# Clock_Distribution.net
KiCad netlist of a schematic drawn in Altium Designer
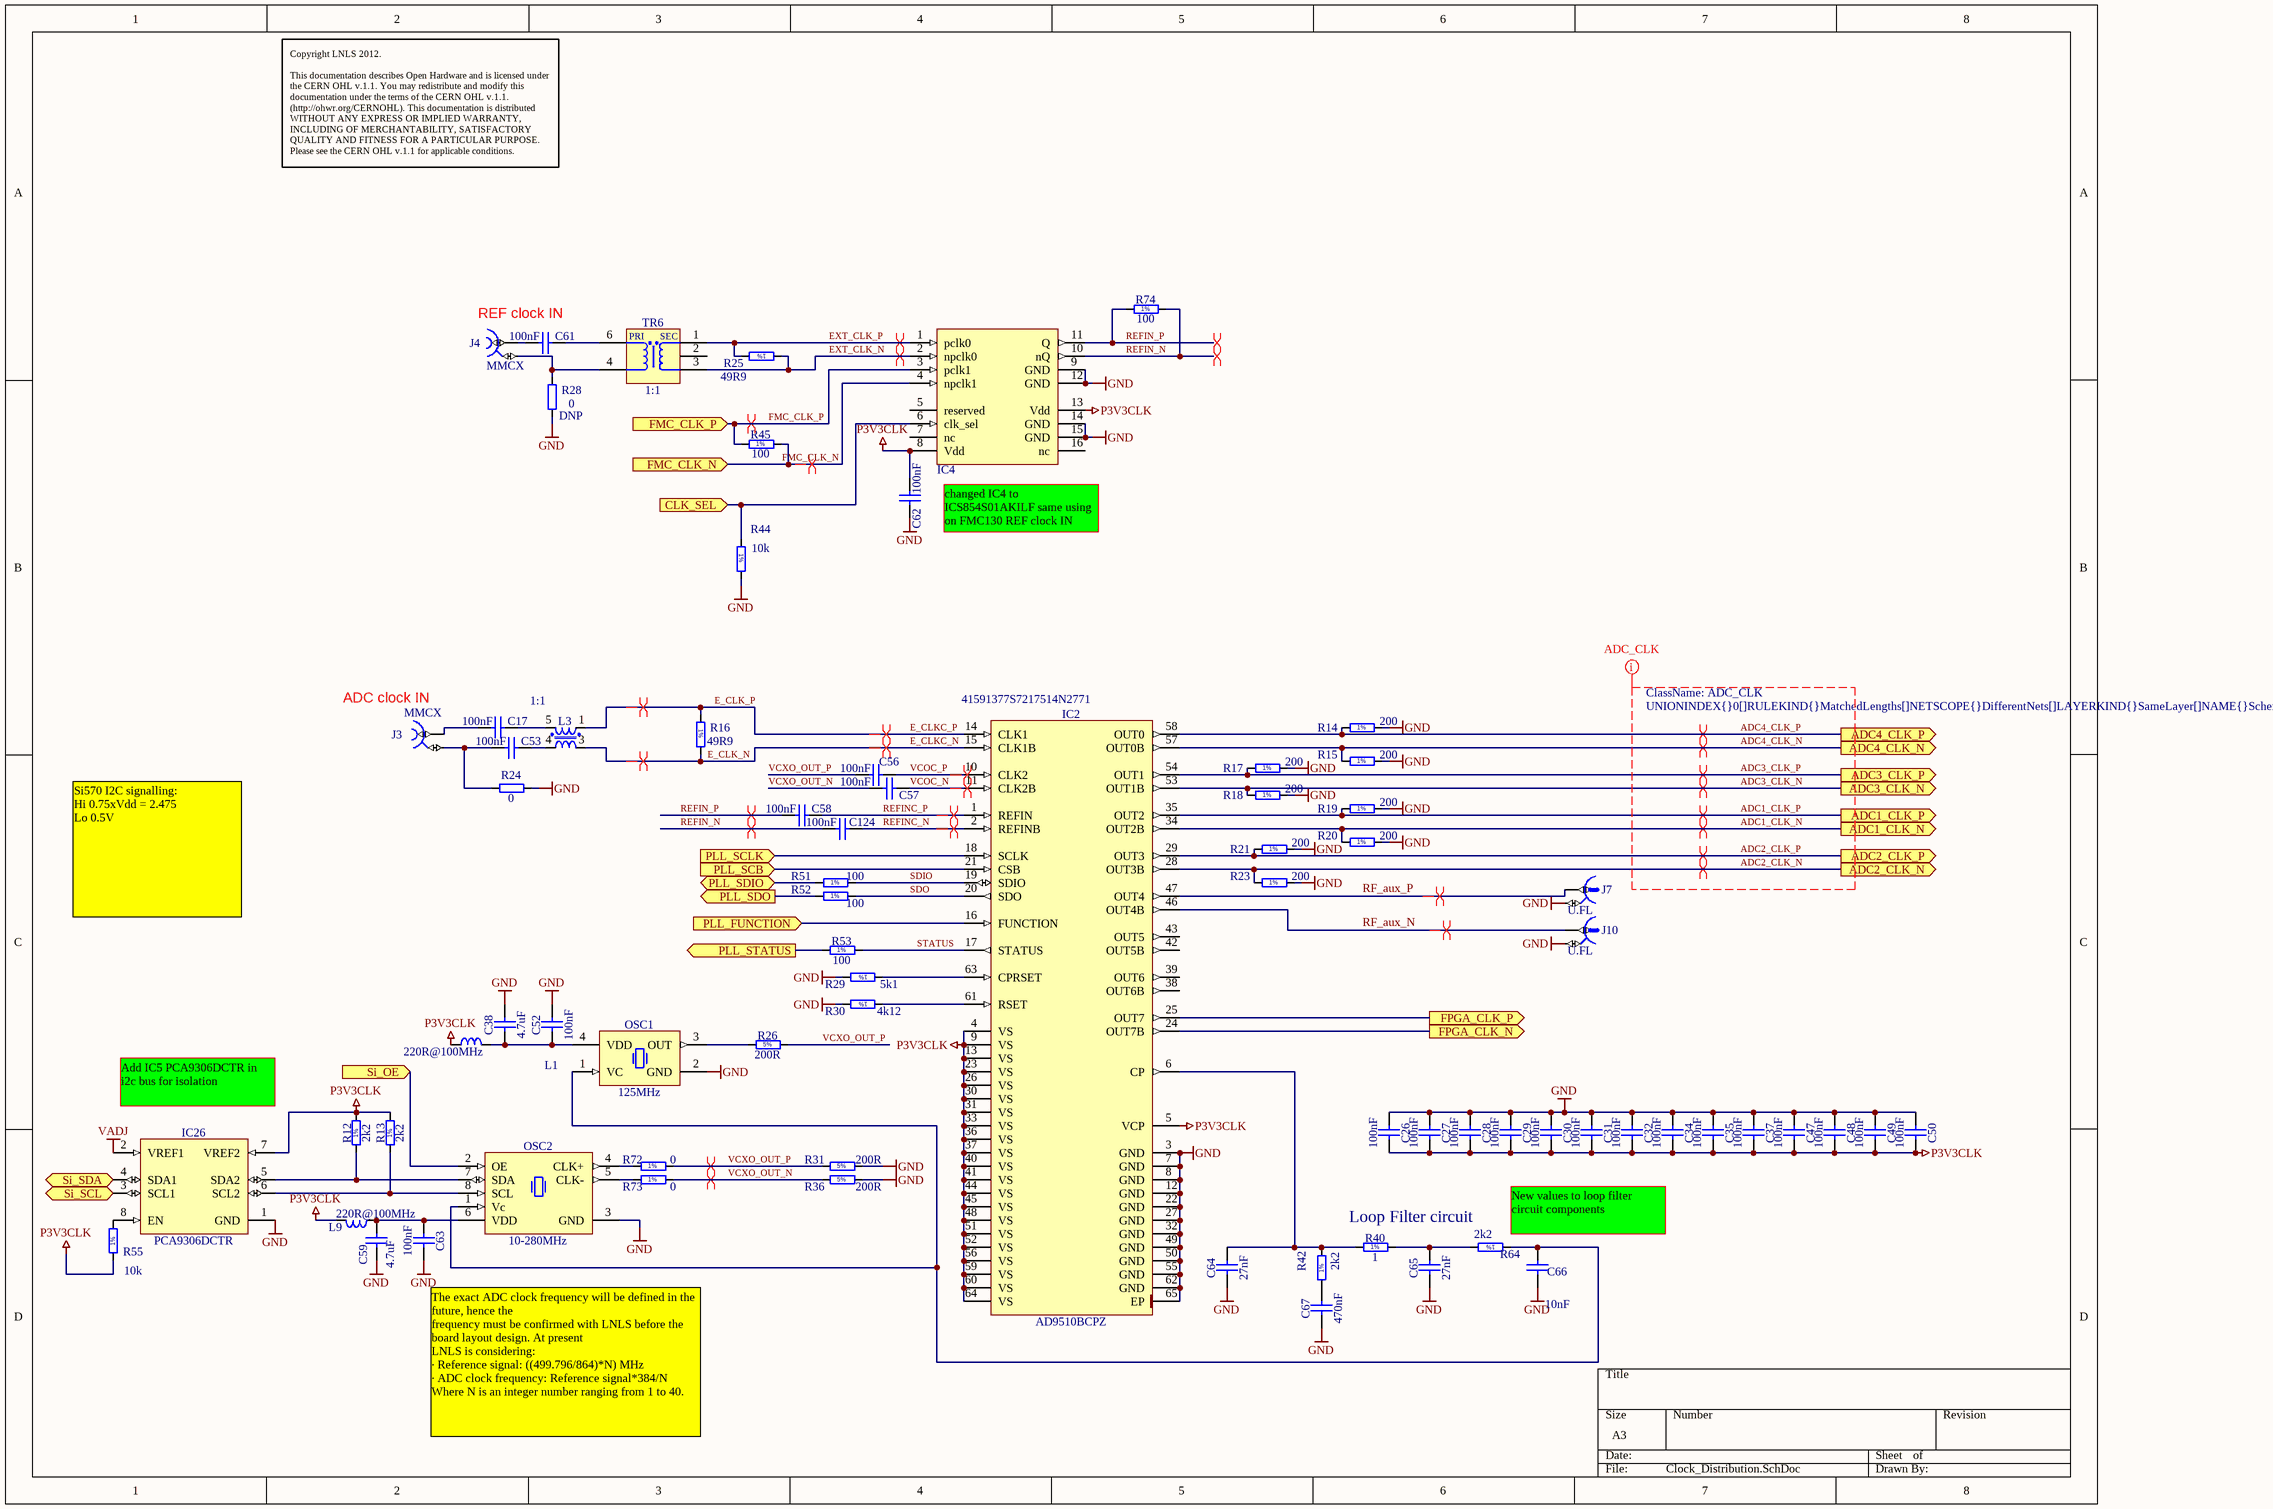
[diagram p0: Clock_Distribution.SchDoc]

(export (version "E")
  (design (tool "Eeschema 10.0.6"))
  (components
    (comp (ref "C17")
      (value "100nF")
      (footprint "CAPC0603X33N")
      (description "Non-polarised capacitor")
      (fields
        (field (name "PART NUMBER") "CC0201_100NF_6.3V_10%_X5R")
        (field (name "VOLTAGE") "6.3V")
        (field (name "AUTHOR") "CERN DEM JLC")
      )
      (libsource (lib "Capacitors") (part "Capacitor - non polarized"))
    )
    (comp (ref "C26")
      (value "100nF")
      (footprint "CAPC0603X33N")
      (description "Non-polarised capacitor")
      (fields
        (field (name "PART NUMBER") "CC0201_100NF_6.3V_10%_X5R")
        (field (name "VOLTAGE") "6.3V")
        (field (name "AUTHOR") "CERN DEM JLC")
      )
      (libsource (lib "Capacitors") (part "Capacitor - non polarized"))
    )
    (comp (ref "C27")
      (value "100nF")
      (footprint "CAPC0603X33N")
      (description "Non-polarised capacitor")
      (fields
        (field (name "PART NUMBER") "CC0201_100NF_6.3V_10%_X5R")
        (field (name "VOLTAGE") "6.3V")
        (field (name "AUTHOR") "CERN DEM JLC")
      )
      (libsource (lib "Capacitors") (part "Capacitor - non polarized"))
    )
    (comp (ref "C28")
      (value "100nF")
      (footprint "CAPC0603X33N")
      (description "Non-polarised capacitor")
      (fields
        (field (name "PART NUMBER") "CC0201_100NF_6.3V_10%_X5R")
        (field (name "VOLTAGE") "6.3V")
        (field (name "AUTHOR") "CERN DEM JLC")
      )
      (libsource (lib "Capacitors") (part "Capacitor - non polarized"))
    )
    (comp (ref "C29")
      (value "100nF")
      (footprint "CAPC0603X33N")
      (description "Non-polarised capacitor")
      (fields
        (field (name "PART NUMBER") "CC0201_100NF_6.3V_10%_X5R")
        (field (name "VOLTAGE") "6.3V")
        (field (name "AUTHOR") "CERN DEM JLC")
      )
      (libsource (lib "Capacitors") (part "Capacitor - non polarized"))
    )
    (comp (ref "C30")
      (value "100nF")
      (footprint "CAPC0603X33N")
      (description "Non-polarised capacitor")
      (fields
        (field (name "PART NUMBER") "CC0201_100NF_6.3V_10%_X5R")
        (field (name "VOLTAGE") "6.3V")
        (field (name "AUTHOR") "CERN DEM JLC")
      )
      (libsource (lib "Capacitors") (part "Capacitor - non polarized"))
    )
    (comp (ref "C31")
      (value "100nF")
      (footprint "CAPC0603X33N")
      (description "Non-polarised capacitor")
      (fields
        (field (name "PART NUMBER") "CC0201_100NF_6.3V_10%_X5R")
        (field (name "VOLTAGE") "6.3V")
        (field (name "AUTHOR") "CERN DEM JLC")
      )
      (libsource (lib "Capacitors") (part "Capacitor - non polarized"))
    )
    (comp (ref "C32")
      (value "100nF")
      (footprint "CAPC0603X33N")
      (description "Non-polarised capacitor")
      (fields
        (field (name "PART NUMBER") "CC0201_100NF_6.3V_10%_X5R")
        (field (name "VOLTAGE") "6.3V")
        (field (name "AUTHOR") "CERN DEM JLC")
      )
      (libsource (lib "Capacitors") (part "Capacitor - non polarized"))
    )
    (comp (ref "C34")
      (value "100nF")
      (footprint "CAPC0603X33N")
      (description "Non-polarised capacitor")
      (fields
        (field (name "PART NUMBER") "CC0201_100NF_6.3V_10%_X5R")
        (field (name "VOLTAGE") "6.3V")
        (field (name "AUTHOR") "CERN DEM JLC")
      )
      (libsource (lib "Capacitors") (part "Capacitor - non polarized"))
    )
    (comp (ref "C35")
      (value "100nF")
      (footprint "CAPC0603X33N")
      (description "Non-polarised capacitor")
      (fields
        (field (name "PART NUMBER") "CC0201_100NF_6.3V_10%_X5R")
        (field (name "VOLTAGE") "6.3V")
        (field (name "AUTHOR") "CERN DEM JLC")
      )
      (libsource (lib "Capacitors") (part "Capacitor - non polarized"))
    )
    (comp (ref "C37")
      (value "100nF")
      (footprint "CAPC0603X33N")
      (description "Non-polarised capacitor")
      (fields
        (field (name "PART NUMBER") "CC0201_100NF_6.3V_10%_X5R")
        (field (name "VOLTAGE") "6.3V")
        (field (name "AUTHOR") "CERN DEM JLC")
      )
      (libsource (lib "Capacitors") (part "Capacitor - non polarized"))
    )
    (comp (ref "C38")
      (value "4.7uF")
      (footprint "CAPC1608X87N")
      (description "Non-polarised capacitor")
      (fields
        (field (name "PART NUMBER") "CC0603_4.7UF_6.3V_10%_X5R")
        (field (name "VOLTAGE") "6.3V")
        (field (name "AUTHOR") "CERN DEM JLC")
      )
      (libsource (lib "Capacitors") (part "Capacitor - non polarized"))
    )
    (comp (ref "C47")
      (value "100nF")
      (footprint "CAPC0603X33N")
      (description "Non-polarised capacitor")
      (fields
        (field (name "PART NUMBER") "CC0201_100NF_6.3V_10%_X5R")
        (field (name "VOLTAGE") "6.3V")
        (field (name "AUTHOR") "CERN DEM JLC")
      )
      (libsource (lib "Capacitors") (part "Capacitor - non polarized"))
    )
    (comp (ref "C48")
      (value "100nF")
      (footprint "CAPC0603X33N")
      (description "Non-polarised capacitor")
      (fields
        (field (name "PART NUMBER") "CC0201_100NF_6.3V_10%_X5R")
        (field (name "VOLTAGE") "6.3V")
        (field (name "AUTHOR") "CERN DEM JLC")
      )
      (libsource (lib "Capacitors") (part "Capacitor - non polarized"))
    )
    (comp (ref "C49")
      (value "100nF")
      (footprint "CAPC0603X33N")
      (description "Non-polarised capacitor")
      (fields
        (field (name "PART NUMBER") "CC0201_100NF_6.3V_10%_X5R")
        (field (name "VOLTAGE") "6.3V")
        (field (name "AUTHOR") "CERN DEM JLC")
      )
      (libsource (lib "Capacitors") (part "Capacitor - non polarized"))
    )
    (comp (ref "C50")
      (value "100nF")
      (footprint "CAPC0603X33N")
      (description "Non-polarised capacitor")
      (fields
        (field (name "PART NUMBER") "CC0201_100NF_6.3V_10%_X5R")
        (field (name "VOLTAGE") "6.3V")
        (field (name "AUTHOR") "CERN DEM JLC")
      )
      (libsource (lib "Capacitors") (part "Capacitor - non polarized"))
    )
    (comp (ref "C52")
      (value "100nF")
      (footprint "CAPC0603X33N")
      (description "Non-polarised capacitor")
      (fields
        (field (name "PART NUMBER") "CC0201_100NF_6.3V_10%_X5R")
        (field (name "VOLTAGE") "6.3V")
        (field (name "AUTHOR") "CERN DEM JLC")
      )
      (libsource (lib "Capacitors") (part "Capacitor - non polarized"))
    )
    (comp (ref "C53")
      (value "100nF")
      (footprint "CAPC0603X33N")
      (description "Non-polarised capacitor")
      (fields
        (field (name "PART NUMBER") "CC0201_100NF_6.3V_10%_X5R")
        (field (name "VOLTAGE") "6.3V")
        (field (name "AUTHOR") "CERN DEM JLC")
      )
      (libsource (lib "Capacitors") (part "Capacitor - non polarized"))
    )
    (comp (ref "C56")
      (value "100nF")
      (footprint "CAPC0603X33N")
      (description "Non-polarised capacitor")
      (fields
        (field (name "PART NUMBER") "CC0201_100NF_6.3V_10%_X5R")
        (field (name "VOLTAGE") "6.3V")
        (field (name "AUTHOR") "CERN DEM JLC")
      )
      (libsource (lib "Capacitors") (part "Capacitor - non polarized"))
    )
    (comp (ref "C57")
      (value "100nF")
      (footprint "CAPC0603X33N")
      (description "Non-polarised capacitor")
      (fields
        (field (name "PART NUMBER") "CC0201_100NF_6.3V_10%_X5R")
        (field (name "VOLTAGE") "6.3V")
        (field (name "AUTHOR") "CERN DEM JLC")
      )
      (libsource (lib "Capacitors") (part "Capacitor - non polarized"))
    )
    (comp (ref "C58")
      (value "100nF")
      (footprint "CAPC0603X33N")
      (description "Non-polarised capacitor")
      (fields
        (field (name "PART NUMBER") "CC0201_100NF_6.3V_10%_X5R")
        (field (name "VOLTAGE") "6.3V")
        (field (name "AUTHOR") "CERN DEM JLC")
      )
      (libsource (lib "Capacitors") (part "Capacitor - non polarized"))
    )
    (comp (ref "C59")
      (value "4.7uF")
      (footprint "CAPC1608X87N")
      (description "Non-polarised capacitor")
      (fields
        (field (name "PART NUMBER") "CC0603_4.7UF_6.3V_10%_X5R")
        (field (name "VOLTAGE") "6.3V")
        (field (name "AUTHOR") "CERN DEM JLC")
      )
      (libsource (lib "Capacitors") (part "Capacitor - non polarized"))
    )
    (comp (ref "C61")
      (value "100nF")
      (footprint "CAPC0603X33N")
      (description "Non-polarised capacitor")
      (fields
        (field (name "PART NUMBER") "CC0201_100NF_6.3V_10%_X5R")
        (field (name "VOLTAGE") "6.3V")
        (field (name "AUTHOR") "CERN DEM JLC")
      )
      (libsource (lib "Capacitors") (part "Capacitor - non polarized"))
    )
    (comp (ref "C62")
      (value "100nF")
      (footprint "CAPC0603X33N")
      (description "Non-polarised capacitor")
      (fields
        (field (name "PART NUMBER") "CC0201_100NF_6.3V_10%_X5R")
        (field (name "VOLTAGE") "6.3V")
        (field (name "AUTHOR") "CERN DEM JLC")
      )
      (libsource (lib "Capacitors") (part "Capacitor - non polarized"))
    )
    (comp (ref "C63")
      (value "100nF")
      (footprint "CAPC0603X33N")
      (description "Non-polarised capacitor")
      (fields
        (field (name "PART NUMBER") "CC0201_100NF_6.3V_10%_X5R")
        (field (name "VOLTAGE") "6.3V")
        (field (name "AUTHOR") "CERN DEM JLC")
      )
      (libsource (lib "Capacitors") (part "Capacitor - non polarized"))
    )
    (comp (ref "C64")
      (value "27nF")
      (footprint "CAPC1608X87N")
      (description "Non-polarised capacitor")
      (fields
        (field (name "PART NUMBER") "CC0603_27NF_25V_10%_X7R")
        (field (name "VOLTAGE") "25V")
        (field (name "AUTHOR") "CERN DEM JLC")
      )
      (libsource (lib "Capacitors") (part "Capacitor - non polarized"))
    )
    (comp (ref "C65")
      (value "27nF")
      (footprint "CAPC1608X87N")
      (description "Non-polarised capacitor")
      (fields
        (field (name "PART NUMBER") "CC0603_27NF_25V_10%_X7R")
        (field (name "VOLTAGE") "25V")
        (field (name "AUTHOR") "CERN DEM JLC")
      )
      (libsource (lib "Capacitors") (part "Capacitor - non polarized"))
    )
    (comp (ref "C66")
      (value "10nF")
      (footprint "CAPC0603X33N")
      (description "Non-polarised capacitor")
      (fields
        (field (name "PART NUMBER") "CC0201_10NF_10V_10%_X7R")
        (field (name "VOLTAGE") "10V")
        (field (name "AUTHOR") "LNLS DIG GBMB")
      )
      (libsource (lib "Capacitors") (part "Capacitor - non polarized"))
    )
    (comp (ref "C67")
      (value "470nF")
      (footprint "CAPC1608X87N")
      (description "Non-polarised capacitor")
      (fields
        (field (name "PART NUMBER") "CC0603_470NF_16V_10%_X5R")
        (field (name "VOLTAGE") "16V")
        (field (name "AUTHOR") "CERN DEM JLC")
      )
      (libsource (lib "Capacitors") (part "Capacitor - non polarized"))
    )
    (comp (ref "C124")
      (value "100nF")
      (footprint "CAPC0603X33N")
      (description "Non-polarised capacitor")
      (fields
        (field (name "PART NUMBER") "CC0201_100NF_6.3V_10%_X5R")
        (field (name "VOLTAGE") "6.3V")
        (field (name "AUTHOR") "CERN DEM JLC")
      )
      (libsource (lib "Capacitors") (part "Capacitor - non polarized"))
    )
    (comp (ref "IC2")
      (value "AD9510BCPZ")
      (footprint "QFN50P900X900X100-65N-S485")
      (description "1.2 GHz Clock Distribution IC, PLL Core, Dividers, Delay Adjust, Eight Outputs")
      (fields
        (field (name "MANUFACTURER") "ANALOG DEVICES")
        (field (name "SUPPLIER PART NUMBER 1") "41591377S7217514N2771")
        (field (name "AUTHOR") "CERN DEM JLC")
      )
      (libsource (lib "ICs And Semiconductors") (part "AD9510"))
    )
    (comp (ref "IC4")
      (value "ICS854S01AKILF")
      (footprint "QFN50P300x300x100-17N-S140")
      (description "2:1 Differential-to-LVDS Multiplexer")
      (fields
        (field (name "MANUFACTURER") "INTEGRATED DEVICE TECHNOLOGY (IDT)")
        (field (name "AUTHOR") "LNLS DIG GBMB")
      )
      (libsource (lib "ICs And Semiconductors") (part "ICS854S01l"))
    )
    (comp (ref "IC26")
      (value "PCA9306DCTR")
      (footprint "SOP65P400X130-8N")
      (description "Dual Bidirectional I2C Bus And SMBus Voltage-Level Translator")
      (fields (field (name "MANUFACTURER") "TEXAS INSTRUMENTS") (field (name "AUTHOR") "CERN DEM JLC"))
      (libsource (lib "ICs And Semiconductors") (part "PCA9306DC"))
    )
    (comp (ref "J3")
      (value "Coax_1Female_1Shield")
      (footprint "HUBER-SUHNER_85_MMCX-50-0-1/111 OH")
      (fields
        (field (name "PART NUMBER") "HUBER-SUHNER_85_MMCX-50-0-1/111 OH")
        (field (name "FAMILY") "MMCX")
        (field (name "MANUFACTURER") "HUBER+SUHNER")
        (field (name "MANUFACTURER PART NUMBER") "85_MMCX-50-0-1/111 OH")
        (field (name "AUTHOR") "CERN DEM JLC")
      )
      (libsource (lib "Connectors") (part "Coax_1Female_1Shield"))
    )
    (comp (ref "J4")
      (value "Coax_1Female_1Shield")
      (footprint "HUBER-SUHNER_85_MMCX-50-0-1/111 OH")
      (fields
        (field (name "PART NUMBER") "HUBER-SUHNER_85_MMCX-50-0-1/111 OH")
        (field (name "FAMILY") "MMCX")
        (field (name "MANUFACTURER") "HUBER+SUHNER")
        (field (name "MANUFACTURER PART NUMBER") "85_MMCX-50-0-1/111 OH")
        (field (name "AUTHOR") "CERN DEM JLC")
      )
      (libsource (lib "Connectors") (part "Coax_1Female_1Shield"))
    )
    (comp (ref "J7")
      (value "U.FL")
      (footprint "HIROSE_U.FL-R-SMT-1(10)")
      (fields
        (field (name "PART NUMBER") "HIROSE_U.FL-R-SMT-1(10)")
        (field (name "MANUFACTURER") "HIROSE (HRS)")
        (field (name "MANUFACTURER PART NUMBER") "U.FL-R-SMT-1(10)")
        (field (name "AUTHOR") "CERN DEM JLC")
      )
      (libsource (lib "Connectors") (part "Coax_1Male_1Shield"))
    )
    (comp (ref "J10")
      (value "U.FL")
      (footprint "HIROSE_U.FL-R-SMT-1(10)")
      (fields
        (field (name "PART NUMBER") "HIROSE_U.FL-R-SMT-1(10)")
        (field (name "MANUFACTURER") "HIROSE (HRS)")
        (field (name "MANUFACTURER PART NUMBER") "U.FL-R-SMT-1(10)")
        (field (name "AUTHOR") "CERN DEM JLC")
      )
      (libsource (lib "Connectors") (part "Coax_1Male_1Shield"))
    )
    (comp (ref "L1")
      (value "220R@100MHz")
      (footprint "INDC1005X55N")
      (description "Inductor")
      (fields
        (field (name "PART NUMBER") "IND0402_MURATA_BLM15HB221SN1")
        (field (name "POWER") "250mA")
        (field (name "AUTHOR") "CERN DEM JLC")
      )
      (libsource (lib "Inductors & Transformers") (part "Inductor"))
    )
    (comp (ref "L3")
      (value "1:1")
      (footprint "XFMR_MA-COM_SM-22 (H260)")
      (description "MA-COM E-Serie RF 1:1 Transmission Line Ttransformer 4.5-3000MHz")
      (fields
        (field (name "PART NUMBER") "XFMR_MA-COM_MABA-007159-000000")
        (field (name "MANUFACTURER") "MA-COM TECHNOLOGY")
        (field (name "AUTHOR") "CERN DEM JLC")
      )
      (libsource (lib "Inductors & Transformers") (part "XFMR_MA-COM_MABA-007159-000000"))
    )
    (comp (ref "L9")
      (value "220R@100MHz")
      (footprint "INDC1005X55N")
      (description "Inductor")
      (fields
        (field (name "PART NUMBER") "IND0402_MURATA_BLM15HB221SN1")
        (field (name "POWER") "250mA")
        (field (name "AUTHOR") "CERN DEM JLC")
      )
      (libsource (lib "Inductors & Transformers") (part "Inductor"))
    )
    (comp (ref "OSC1")
      (value "125MHz")
      (footprint "OSC_CRYSTEK_CVHD-950")
      (description "Oscillator 4 pins 1=VC 2=GND 3=OUT 4=VDD")
      (fields
        (field (name "PART NUMBER") "OSC_250MHZ_CRYSTEK_CVHD-940-250.000")
        (field (name "MANUFACTURER") "CRYSTEK CRYSTAL")
        (field (name "AUTHOR") "CERN DEM JLC")
      )
      (libsource (lib "ICs And Semiconductors") (part "Oscillator 1VC 2GND 3OUT 4VDD"))
    )
    (comp (ref "OSC2")
      (value "10-280MHz")
      (footprint "OSC_SILICON-LAB_SI571")
      (description "Any-Rate I2C Programmable XO Oscillator Si571 Serie")
      (fields
        (field (name "PART NUMBER") "OSC_10-280MHZ_SILICON-LAB_Si571AJC000337DG")
        (field (name "MANUFACTURER") "SILICON LABS")
        (field (name "AUTHOR") "CERN DEM JLC")
      )
      (libsource (lib "ICs And Semiconductors") (part "Oscillator SILICON-LAB_Si571"))
    )
    (comp (ref "R12")
      (value "2k2")
      (footprint "RESC1005X40N")
      (description "Resistor - 1%")
      (fields
        (field (name "PART NUMBER") "R0402_2K2_1%_0.0625W_100PPM")
        (field (name "POWER") "0.0625W")
        (field (name "AUTHOR") "CERN DEM JLC")
      )
      (libsource (lib "Resistors") (part "Resistor - 1%"))
    )
    (comp (ref "R13")
      (value "2k2")
      (footprint "RESC1005X40N")
      (description "Resistor - 1%")
      (fields
        (field (name "PART NUMBER") "R0402_2K2_1%_0.0625W_100PPM")
        (field (name "POWER") "0.0625W")
        (field (name "AUTHOR") "CERN DEM JLC")
      )
      (libsource (lib "Resistors") (part "Resistor - 1%"))
    )
    (comp (ref "R14")
      (value "200")
      (footprint "RESC1005X40N")
      (description "Resistor - 1%")
      (fields
        (field (name "PART NUMBER") "R0402_200R_1%_0.0625W_100PPM")
        (field (name "POWER") "0.0625W")
        (field (name "AUTHOR") "CERN DEM JLC")
      )
      (libsource (lib "Resistors") (part "Resistor - 1%"))
    )
    (comp (ref "R15")
      (value "200")
      (footprint "RESC1005X40N")
      (description "Resistor - 1%")
      (fields
        (field (name "PART NUMBER") "R0402_200R_1%_0.0625W_100PPM")
        (field (name "POWER") "0.0625W")
        (field (name "AUTHOR") "CERN DEM JLC")
      )
      (libsource (lib "Resistors") (part "Resistor - 1%"))
    )
    (comp (ref "R16")
      (value "49R9")
      (footprint "RESC1005X40N")
      (description "Resistor - 1%")
      (fields
        (field (name "PART NUMBER") "R0402_49R9_1%_0.0625W_100PPM")
        (field (name "POWER") "0.0625W")
        (field (name "AUTHOR") "CERN DEM JLC")
      )
      (libsource (lib "Resistors") (part "Resistor - 1%"))
    )
    (comp (ref "R17")
      (value "200")
      (footprint "RESC1005X40N")
      (description "Resistor - 1%")
      (fields
        (field (name "PART NUMBER") "R0402_200R_1%_0.0625W_100PPM")
        (field (name "POWER") "0.0625W")
        (field (name "AUTHOR") "CERN DEM JLC")
      )
      (libsource (lib "Resistors") (part "Resistor - 1%"))
    )
    (comp (ref "R18")
      (value "200")
      (footprint "RESC1005X40N")
      (description "Resistor - 1%")
      (fields
        (field (name "PART NUMBER") "R0402_200R_1%_0.0625W_100PPM")
        (field (name "POWER") "0.0625W")
        (field (name "AUTHOR") "CERN DEM JLC")
      )
      (libsource (lib "Resistors") (part "Resistor - 1%"))
    )
    (comp (ref "R19")
      (value "200")
      (footprint "RESC1005X40N")
      (description "Resistor - 1%")
      (fields
        (field (name "PART NUMBER") "R0402_200R_1%_0.0625W_100PPM")
        (field (name "POWER") "0.0625W")
        (field (name "AUTHOR") "CERN DEM JLC")
      )
      (libsource (lib "Resistors") (part "Resistor - 1%"))
    )
    (comp (ref "R20")
      (value "200")
      (footprint "RESC1005X40N")
      (description "Resistor - 1%")
      (fields
        (field (name "PART NUMBER") "R0402_200R_1%_0.0625W_100PPM")
        (field (name "POWER") "0.0625W")
        (field (name "AUTHOR") "CERN DEM JLC")
      )
      (libsource (lib "Resistors") (part "Resistor - 1%"))
    )
    (comp (ref "R21")
      (value "200")
      (footprint "RESC1005X40N")
      (description "Resistor - 1%")
      (fields
        (field (name "PART NUMBER") "R0402_200R_1%_0.0625W_100PPM")
        (field (name "POWER") "0.0625W")
        (field (name "AUTHOR") "CERN DEM JLC")
      )
      (libsource (lib "Resistors") (part "Resistor - 1%"))
    )
    (comp (ref "R23")
      (value "200")
      (footprint "RESC1005X40N")
      (description "Resistor - 1%")
      (fields
        (field (name "PART NUMBER") "R0402_200R_1%_0.0625W_100PPM")
        (field (name "POWER") "0.0625W")
        (field (name "AUTHOR") "CERN DEM JLC")
      )
      (libsource (lib "Resistors") (part "Resistor - 1%"))
    )
    (comp (ref "R24")
      (value "0")
      (footprint "RESC1005X40N")
      (description "Resistor")
      (fields
        (field (name "PART NUMBER") "R0402_0R_JUMPER")
        (field (name "MANUFACTURER") "GENERIC")
        (field (name "AUTHOR") "CERN DEM JLC")
      )
      (libsource (lib "Resistors") (part "Resistor"))
    )
    (comp (ref "R25")
      (value "49R9")
      (footprint "RESC1005X40N")
      (description "Resistor - 1%")
      (fields
        (field (name "PART NUMBER") "R0402_49R9_1%_0.0625W_100PPM")
        (field (name "POWER") "0.0625W")
        (field (name "AUTHOR") "CERN DEM JLC")
      )
      (libsource (lib "Resistors") (part "Resistor - 1%"))
    )
    (comp (ref "R26")
      (value "200R")
      (footprint "RESC1005X40N")
      (description "Resistor - 5%")
      (fields
        (field (name "PART NUMBER") "R0402_200R_5%_0.0625W_100PPM")
        (field (name "TOLERANCE") "5%")
        (field (name "AUTHOR") "CERN DEM JLC")
      )
      (libsource (lib "Resistors") (part "Resistor - 5%"))
    )
    (comp (ref "R28")
      (value "0")
      (footprint "RESC1005X40N")
      (description "Resistor")
      (fields
        (field (name "PART NUMBER") "R0402_0R_JUMPER")
        (field (name "MANUFACTURER") "GENERIC")
        (field (name "MOUNTED") "DNP")
        (field (name "AUTHOR") "CERN DEM JLC")
      )
      (libsource (lib "Resistors") (part "Resistor"))
    )
    (comp (ref "R29")
      (value "5k1")
      (footprint "RESC1005X40N")
      (description "Resistor - 1%")
      (fields
        (field (name "PART NUMBER") "R0402_5K1_1%_0.0625W_100PPM")
        (field (name "POWER") "0.0625W")
        (field (name "AUTHOR") "CERN DEM JLC")
      )
      (libsource (lib "Resistors") (part "Resistor - 1%"))
    )
    (comp (ref "R30")
      (value "4k12")
      (footprint "RESC1005X40N")
      (description "Resistor - 1%")
      (fields
        (field (name "PART NUMBER") "R0402_4K12_1%_0.0625W_100PPM")
        (field (name "POWER") "0.0625W")
        (field (name "AUTHOR") "CERN DEM JLC")
      )
      (libsource (lib "Resistors") (part "Resistor - 1%"))
    )
    (comp (ref "R31")
      (value "200R")
      (footprint "RESC1005X40N")
      (description "Resistor - 5%")
      (fields
        (field (name "PART NUMBER") "R0402_200R_5%_0.0625W_100PPM")
        (field (name "TOLERANCE") "5%")
        (field (name "AUTHOR") "CERN DEM JLC")
      )
      (libsource (lib "Resistors") (part "Resistor - 5%"))
    )
    (comp (ref "R36")
      (value "200R")
      (footprint "RESC1005X40N")
      (description "Resistor - 5%")
      (fields
        (field (name "PART NUMBER") "R0402_200R_5%_0.0625W_100PPM")
        (field (name "TOLERANCE") "5%")
        (field (name "AUTHOR") "CERN DEM JLC")
      )
      (libsource (lib "Resistors") (part "Resistor - 5%"))
    )
    (comp (ref "R40")
      (value "1")
      (footprint "RESC1005X40N")
      (description "Resistor - 1%")
      (fields
        (field (name "PART NUMBER") "R0402_1R_1%_0.0625W_200PPM")
        (field (name "POWER") "0.0625W")
        (field (name "AUTHOR") "CERN DEM JLC")
      )
      (libsource (lib "Resistors") (part "Resistor - 1%"))
    )
    (comp (ref "R42")
      (value "2k2")
      (footprint "RESC1005X40N")
      (description "Resistor - 1%")
      (fields
        (field (name "PART NUMBER") "R0402_2K2_1%_0.0625W_100PPM")
        (field (name "POWER") "0.0625W")
        (field (name "AUTHOR") "CERN DEM JLC")
      )
      (libsource (lib "Resistors") (part "Resistor - 1%"))
    )
    (comp (ref "R44")
      (value "10k")
      (footprint "RESC1005X40N")
      (description "Resistor - 1%")
      (fields
        (field (name "PART NUMBER") "R0402_10K_1%_0.0625W_100PPM")
        (field (name "POWER") "0.0625W")
        (field (name "AUTHOR") "CERN DEM JLC")
      )
      (libsource (lib "Resistors") (part "Resistor - 1%"))
    )
    (comp (ref "R45")
      (value "100")
      (footprint "RESC1005X40N")
      (description "Resistor - 1%")
      (fields
        (field (name "PART NUMBER") "R0402_100R_1%_0.0625W_100PPM")
        (field (name "POWER") "0.0625W")
        (field (name "AUTHOR") "CERN DEM JLC")
      )
      (libsource (lib "Resistors") (part "Resistor - 1%"))
    )
    (comp (ref "R51")
      (value "100")
      (footprint "RESC1005X40N")
      (description "Resistor - 1%")
      (fields
        (field (name "PART NUMBER") "R0402_100R_1%_0.0625W_100PPM")
        (field (name "POWER") "0.0625W")
        (field (name "AUTHOR") "CERN DEM JLC")
      )
      (libsource (lib "Resistors") (part "Resistor - 1%"))
    )
    (comp (ref "R52")
      (value "100")
      (footprint "RESC1005X40N")
      (description "Resistor - 1%")
      (fields
        (field (name "PART NUMBER") "R0402_100R_1%_0.0625W_100PPM")
        (field (name "POWER") "0.0625W")
        (field (name "AUTHOR") "CERN DEM JLC")
      )
      (libsource (lib "Resistors") (part "Resistor - 1%"))
    )
    (comp (ref "R53")
      (value "100")
      (footprint "RESC1005X40N")
      (description "Resistor - 1%")
      (fields
        (field (name "PART NUMBER") "R0402_100R_1%_0.0625W_100PPM")
        (field (name "POWER") "0.0625W")
        (field (name "AUTHOR") "CERN DEM JLC")
      )
      (libsource (lib "Resistors") (part "Resistor - 1%"))
    )
    (comp (ref "R55")
      (value "10k")
      (footprint "RESC1005X40N")
      (description "Resistor - 1%")
      (fields
        (field (name "PART NUMBER") "R0402_10K_1%_0.0625W_100PPM")
        (field (name "POWER") "0.0625W")
        (field (name "AUTHOR") "CERN DEM JLC")
      )
      (libsource (lib "Resistors") (part "Resistor - 1%"))
    )
    (comp (ref "R64")
      (value "2k2")
      (footprint "RESC1005X40N")
      (description "Resistor - 1%")
      (fields
        (field (name "PART NUMBER") "R0402_2K2_1%_0.0625W_100PPM")
        (field (name "POWER") "0.0625W")
        (field (name "AUTHOR") "CERN DEM JLC")
      )
      (libsource (lib "Resistors") (part "Resistor - 1%"))
    )
    (comp (ref "R72")
      (value "0")
      (footprint "RESC1005X40N")
      (description "Resistor - 1%")
      (fields
        (field (name "PART NUMBER") "R0402_0R_JUMPER")
        (field (name "MANUFACTURER") "GENERIC")
        (field (name "AUTHOR") "CERN DEM JLC")
      )
      (libsource (lib "Resistors") (part "Resistor - 1%"))
    )
    (comp (ref "R73")
      (value "0")
      (footprint "RESC1005X40N")
      (description "Resistor - 1%")
      (fields
        (field (name "PART NUMBER") "R0402_0R_JUMPER")
        (field (name "MANUFACTURER") "GENERIC")
        (field (name "AUTHOR") "CERN DEM JLC")
      )
      (libsource (lib "Resistors") (part "Resistor - 1%"))
    )
    (comp (ref "R74")
      (value "100")
      (footprint "RESC1005X40N")
      (description "Resistor - 1%")
      (fields
        (field (name "PART NUMBER") "R0402_100R_1%_0.0625W_100PPM")
        (field (name "POWER") "0.0625W")
        (field (name "AUTHOR") "CERN DEM JLC")
      )
      (libsource (lib "Resistors") (part "Resistor - 1%"))
    )
    (comp (ref "TR6")
      (value "1:1")
      (footprint "XFMR_MINI-CIRCUITS_AT224-1")
      (description "50 Ohm  0.4 To 500MHz RF Transformers")
      (fields
        (field (name "PART NUMBER") "XFMR_MINI-CIRCUITS_TC1-1T+")
        (field (name "MANUFACTURER") "MINI-CIRCUITS")
        (field (name "AUTHOR") "CERN DEM JLC")
      )
      (libsource (lib "Inductors & Transformers") (part "XFMR_MINI-CIRCUITS_TC1-1+"))
    )
  )
  (nets
    (net (code "1") (name "/ADC1_CLK_N") (class "Default")
      (node (ref "IC2") (pin "34") (pinfunction "OUT2B_34") (pintype "output"))
      (node (ref "R20") (pin "1") (pinfunction "1_1") (pintype "passive"))
    )
    (net (code "2") (name "/ADC1_CLK_P") (class "Default")
      (node (ref "IC2") (pin "35") (pinfunction "OUT2_35") (pintype "output"))
      (node (ref "R19") (pin "1") (pinfunction "1_1") (pintype "passive"))
    )
    (net (code "3") (name "/ADC2_CLK_N") (class "Default")
      (node (ref "IC2") (pin "28") (pinfunction "OUT3B_28") (pintype "output"))
      (node (ref "R23") (pin "1") (pinfunction "1_1") (pintype "passive"))
    )
    (net (code "4") (name "/ADC2_CLK_P") (class "Default")
      (node (ref "IC2") (pin "29") (pinfunction "OUT3_29") (pintype "output"))
      (node (ref "R21") (pin "1") (pinfunction "1_1") (pintype "passive"))
    )
    (net (code "5") (name "/ADC3_CLK_N") (class "Default")
      (node (ref "IC2") (pin "53") (pinfunction "OUT1B_53") (pintype "output"))
      (node (ref "R18") (pin "1") (pinfunction "1_1") (pintype "passive"))
    )
    (net (code "6") (name "/ADC3_CLK_P") (class "Default")
      (node (ref "IC2") (pin "54") (pinfunction "OUT1_54") (pintype "output"))
      (node (ref "R17") (pin "1") (pinfunction "1_1") (pintype "passive"))
    )
    (net (code "7") (name "/ADC4_CLK_N") (class "Default")
      (node (ref "IC2") (pin "57") (pinfunction "OUT0B_57") (pintype "output"))
      (node (ref "R15") (pin "1") (pinfunction "1_1") (pintype "passive"))
    )
    (net (code "8") (name "/ADC4_CLK_P") (class "Default")
      (node (ref "IC2") (pin "58") (pinfunction "OUT0_58") (pintype "output"))
      (node (ref "R14") (pin "1") (pinfunction "1_1") (pintype "passive"))
    )
    (net (code "9") (name "/CLK_SEL") (class "Default")
      (node (ref "IC4") (pin "6") (pinfunction "clk_sel_6") (pintype "input"))
      (node (ref "R44") (pin "1") (pinfunction "1_1") (pintype "passive"))
    )
    (net (code "10") (name "/EXT_CLK_N") (class "Default")
      (node (ref "IC4") (pin "2") (pinfunction "npclk0_2") (pintype "input"))
      (node (ref "R25") (pin "1") (pinfunction "1_1") (pintype "passive"))
      (node (ref "TR6") (pin "3") (pinfunction "S_3") (pintype "passive"))
    )
    (net (code "11") (name "/EXT_CLK_P") (class "Default")
      (node (ref "IC4") (pin "1") (pinfunction "pclk0_1") (pintype "input"))
      (node (ref "R25") (pin "2") (pinfunction "2_2") (pintype "passive"))
      (node (ref "TR6") (pin "1") (pinfunction "SDOT_1") (pintype "passive"))
    )
    (net (code "12") (name "/E_CLKC_N") (class "Default")
      (node (ref "IC2") (pin "15") (pinfunction "CLK1B_15") (pintype "input"))
      (node (ref "L3") (pin "3") (pinfunction "3_3") (pintype "passive"))
      (node (ref "R16") (pin "2") (pinfunction "2_2") (pintype "passive"))
    )
    (net (code "13") (name "/E_CLKC_P") (class "Default")
      (node (ref "IC2") (pin "14") (pinfunction "CLK1_14") (pintype "input"))
      (node (ref "L3") (pin "1") (pinfunction "1_1") (pintype "passive"))
      (node (ref "R16") (pin "1") (pinfunction "1_1") (pintype "passive"))
    )
    (net (code "14") (name "/FMC_CLK_N") (class "Default")
      (node (ref "IC4") (pin "4") (pinfunction "npclk1_4") (pintype "input"))
      (node (ref "R45") (pin "2") (pinfunction "2_2") (pintype "passive"))
    )
    (net (code "15") (name "/FMC_CLK_P") (class "Default")
      (node (ref "IC4") (pin "3") (pinfunction "pclk1_3") (pintype "input"))
      (node (ref "R45") (pin "1") (pinfunction "1_1") (pintype "passive"))
    )
    (net (code "16") (name "/FPGA_CLK_N") (class "Default")
      (node (ref "IC2") (pin "24") (pinfunction "OUT7B_24") (pintype "output"))
    )
    (net (code "17") (name "/FPGA_CLK_P") (class "Default")
      (node (ref "IC2") (pin "25") (pinfunction "OUT7_25") (pintype "output"))
    )
    (net (code "18") (name "/PLL_FUNCTION") (class "Default")
      (node (ref "IC2") (pin "16") (pinfunction "FUNCTION_16") (pintype "input"))
    )
    (net (code "19") (name "/PLL_SCB") (class "Default")
      (node (ref "IC2") (pin "21") (pinfunction "CSB_21") (pintype "input"))
    )
    (net (code "20") (name "/PLL_SCLK") (class "Default")
      (node (ref "IC2") (pin "18") (pinfunction "SCLK_18") (pintype "input"))
    )
    (net (code "21") (name "/PLL_SDIO") (class "Default")
      (node (ref "R51") (pin "1") (pinfunction "1_1") (pintype "passive"))
    )
    (net (code "22") (name "/PLL_SDO") (class "Default")
      (node (ref "R52") (pin "1") (pinfunction "1_1") (pintype "passive"))
    )
    (net (code "23") (name "/PLL_STATUS") (class "Default")
      (node (ref "R53") (pin "1") (pinfunction "1_1") (pintype "passive"))
    )
    (net (code "24") (name "/REFINC_N") (class "Default")
      (node (ref "C124") (pin "1") (pinfunction "1_1") (pintype "passive"))
      (node (ref "IC2") (pin "2") (pinfunction "REFINB_2") (pintype "input"))
    )
    (net (code "25") (name "/REFINC_P") (class "Default")
      (node (ref "C58") (pin "1") (pinfunction "1_1") (pintype "passive"))
      (node (ref "IC2") (pin "1") (pinfunction "REFIN_1") (pintype "input"))
    )
    (net (code "26") (name "/REFIN_N") (class "Default")
      (node (ref "C124") (pin "2") (pinfunction "2_2") (pintype "passive"))
      (node (ref "IC4") (pin "10") (pinfunction "nQ_10") (pintype "output"))
      (node (ref "R74") (pin "2") (pinfunction "2_2") (pintype "passive"))
    )
    (net (code "27") (name "/REFIN_P") (class "Default")
      (node (ref "C58") (pin "2") (pinfunction "2_2") (pintype "passive"))
      (node (ref "IC4") (pin "11") (pinfunction "Q_11") (pintype "output"))
      (node (ref "R74") (pin "1") (pinfunction "1_1") (pintype "passive"))
    )
    (net (code "28") (name "/RF_aux_N") (class "Default")
      (node (ref "IC2") (pin "46") (pinfunction "OUT4B_46") (pintype "output"))
      (node (ref "J10") (pin "1") (pinfunction "1_1") (pintype "bidirectional"))
    )
    (net (code "29") (name "/RF_aux_P") (class "Default")
      (node (ref "IC2") (pin "47") (pinfunction "OUT4_47") (pintype "output"))
      (node (ref "J7") (pin "1") (pinfunction "1_1") (pintype "bidirectional"))
    )
    (net (code "30") (name "/SDIO") (class "Default")
      (node (ref "IC2") (pin "19") (pinfunction "SDIO_19") (pintype "bidirectional"))
      (node (ref "R51") (pin "2") (pinfunction "2_2") (pintype "passive"))
    )
    (net (code "31") (name "/SDO") (class "Default")
      (node (ref "IC2") (pin "20") (pinfunction "SDO_20") (pintype "output"))
      (node (ref "R52") (pin "2") (pinfunction "2_2") (pintype "passive"))
    )
    (net (code "32") (name "/STATUS") (class "Default")
      (node (ref "IC2") (pin "17") (pinfunction "STATUS_17") (pintype "output"))
      (node (ref "R53") (pin "2") (pinfunction "2_2") (pintype "passive"))
    )
    (net (code "33") (name "/Si_OE") (class "Default")
      (node (ref "OSC2") (pin "2") (pinfunction "OE_2") (pintype "input"))
    )
    (net (code "34") (name "/Si_SCL") (class "Default")
      (node (ref "IC26") (pin "3") (pinfunction "SCL1_3") (pintype "bidirectional"))
    )
    (net (code "35") (name "/Si_SDA") (class "Default")
      (node (ref "IC26") (pin "4") (pinfunction "SDA1_4") (pintype "bidirectional"))
    )
    (net (code "36") (name "/VCOC_N") (class "Default")
      (node (ref "C57") (pin "1") (pinfunction "1_1") (pintype "passive"))
      (node (ref "IC2") (pin "11") (pinfunction "CLK2B_11") (pintype "input"))
    )
    (net (code "37") (name "/VCOC_P") (class "Default")
      (node (ref "C56") (pin "1") (pinfunction "1_1") (pintype "passive"))
      (node (ref "IC2") (pin "10") (pinfunction "CLK2_10") (pintype "input"))
    )
    (net (code "38") (name "/VCXO_OUT_N") (class "Default")
      (node (ref "C57") (pin "2") (pinfunction "2_2") (pintype "passive"))
      (node (ref "R36") (pin "1") (pinfunction "1_1") (pintype "passive"))
      (node (ref "R73") (pin "2") (pinfunction "2_2") (pintype "passive"))
    )
    (net (code "39") (name "/VCXO_OUT_P") (class "Default")
      (node (ref "C56") (pin "2") (pinfunction "2_2") (pintype "passive"))
      (node (ref "R26") (pin "2") (pinfunction "2_2") (pintype "passive"))
      (node (ref "R31") (pin "1") (pinfunction "1_1") (pintype "passive"))
      (node (ref "R72") (pin "2") (pinfunction "2_2") (pintype "passive"))
    )
    (net (code "40") (name "GND") (class "Default")
      (node (ref "C26") (pin "1") (pinfunction "1_1") (pintype "passive"))
      (node (ref "C27") (pin "1") (pinfunction "1_1") (pintype "passive"))
      (node (ref "C28") (pin "1") (pinfunction "1_1") (pintype "passive"))
      (node (ref "C29") (pin "1") (pinfunction "1_1") (pintype "passive"))
      (node (ref "C30") (pin "1") (pinfunction "1_1") (pintype "passive"))
      (node (ref "C31") (pin "1") (pinfunction "1_1") (pintype "passive"))
      (node (ref "C32") (pin "1") (pinfunction "1_1") (pintype "passive"))
      (node (ref "C34") (pin "1") (pinfunction "1_1") (pintype "passive"))
      (node (ref "C35") (pin "1") (pinfunction "1_1") (pintype "passive"))
      (node (ref "C37") (pin "1") (pinfunction "1_1") (pintype "passive"))
      (node (ref "C38") (pin "2") (pinfunction "2_2") (pintype "passive"))
      (node (ref "C47") (pin "1") (pinfunction "1_1") (pintype "passive"))
      (node (ref "C48") (pin "1") (pinfunction "1_1") (pintype "passive"))
      (node (ref "C49") (pin "1") (pinfunction "1_1") (pintype "passive"))
      (node (ref "C50") (pin "1") (pinfunction "1_1") (pintype "passive"))
      (node (ref "C52") (pin "2") (pinfunction "2_2") (pintype "passive"))
      (node (ref "C59") (pin "1") (pinfunction "1_1") (pintype "passive"))
      (node (ref "C62") (pin "1") (pinfunction "1_1") (pintype "passive"))
      (node (ref "C63") (pin "2") (pinfunction "2_2") (pintype "passive"))
      (node (ref "C64") (pin "1") (pinfunction "1_1") (pintype "passive"))
      (node (ref "C65") (pin "1") (pinfunction "1_1") (pintype "passive"))
      (node (ref "C66") (pin "1") (pinfunction "1_1") (pintype "passive"))
      (node (ref "C67") (pin "1") (pinfunction "1_1") (pintype "passive"))
      (node (ref "IC2") (pin "12") (pinfunction "GND_12") (pintype "power_in"))
      (node (ref "IC2") (pin "22") (pinfunction "GND_22") (pintype "power_in"))
      (node (ref "IC2") (pin "27") (pinfunction "GND_27") (pintype "power_in"))
      (node (ref "IC2") (pin "3") (pinfunction "GND_3") (pintype "power_in"))
      (node (ref "IC2") (pin "32") (pinfunction "GND_32") (pintype "power_in"))
      (node (ref "IC2") (pin "49") (pinfunction "GND_49") (pintype "power_in"))
      (node (ref "IC2") (pin "50") (pinfunction "GND_50") (pintype "power_in"))
      (node (ref "IC2") (pin "55") (pinfunction "GND_55") (pintype "power_in"))
      (node (ref "IC2") (pin "62") (pinfunction "GND_62") (pintype "power_in"))
      (node (ref "IC2") (pin "65") (pinfunction "EP_65") (pintype "power_in"))
      (node (ref "IC2") (pin "7") (pinfunction "GND_7") (pintype "power_in"))
      (node (ref "IC2") (pin "8") (pinfunction "GND_8") (pintype "power_in"))
      (node (ref "IC26") (pin "1") (pinfunction "GND_1") (pintype "power_in"))
      (node (ref "IC4") (pin "12") (pinfunction "GND_12") (pintype "passive"))
      (node (ref "IC4") (pin "14") (pinfunction "GND_14") (pintype "passive"))
      (node (ref "IC4") (pin "15") (pinfunction "GND_15") (pintype "passive"))
      (node (ref "IC4") (pin "9") (pinfunction "GND_9") (pintype "passive"))
      (node (ref "J10") (pin "2") (pinfunction "2_2") (pintype "bidirectional"))
      (node (ref "J7") (pin "2") (pinfunction "2_2") (pintype "bidirectional"))
      (node (ref "OSC1") (pin "2") (pinfunction "GND_2") (pintype "power_in"))
      (node (ref "OSC2") (pin "3") (pinfunction "GND_3") (pintype "power_in"))
      (node (ref "R14") (pin "2") (pinfunction "2_2") (pintype "passive"))
      (node (ref "R15") (pin "2") (pinfunction "2_2") (pintype "passive"))
      (node (ref "R17") (pin "2") (pinfunction "2_2") (pintype "passive"))
      (node (ref "R18") (pin "2") (pinfunction "2_2") (pintype "passive"))
      (node (ref "R19") (pin "2") (pinfunction "2_2") (pintype "passive"))
      (node (ref "R20") (pin "2") (pinfunction "2_2") (pintype "passive"))
      (node (ref "R21") (pin "2") (pinfunction "2_2") (pintype "passive"))
      (node (ref "R23") (pin "2") (pinfunction "2_2") (pintype "passive"))
      (node (ref "R24") (pin "2") (pinfunction "2_2") (pintype "passive"))
      (node (ref "R28") (pin "2") (pinfunction "2_2") (pintype "passive"))
      (node (ref "R29") (pin "2") (pinfunction "2_2") (pintype "passive"))
      (node (ref "R30") (pin "2") (pinfunction "2_2") (pintype "passive"))
      (node (ref "R31") (pin "2") (pinfunction "2_2") (pintype "passive"))
      (node (ref "R36") (pin "2") (pinfunction "2_2") (pintype "passive"))
      (node (ref "R44") (pin "2") (pinfunction "2_2") (pintype "passive"))
    )
    (net (code "41") (name "Net-(C17-Pad1)") (class "Default")
      (node (ref "C17") (pin "1") (pinfunction "1_1") (pintype "passive"))
      (node (ref "L3") (pin "5") (pinfunction "5_5") (pintype "passive"))
    )
    (net (code "42") (name "Net-(C17-Pad2)") (class "Default")
      (node (ref "C17") (pin "2") (pinfunction "2_2") (pintype "passive"))
      (node (ref "J3") (pin "1") (pinfunction "1_1") (pintype "bidirectional"))
    )
    (net (code "43") (name "Net-(C53-Pad1)") (class "Default")
      (node (ref "C53") (pin "1") (pinfunction "1_1") (pintype "passive"))
      (node (ref "L3") (pin "4") (pinfunction "4_4") (pintype "passive"))
    )
    (net (code "44") (name "Net-(C53-Pad2)") (class "Default")
      (node (ref "C53") (pin "2") (pinfunction "2_2") (pintype "passive"))
      (node (ref "J3") (pin "2") (pinfunction "2_2") (pintype "bidirectional"))
      (node (ref "R24") (pin "1") (pinfunction "1_1") (pintype "passive"))
    )
    (net (code "45") (name "Net-(C61-Pad2)") (class "Default")
      (node (ref "C61") (pin "2") (pinfunction "2_2") (pintype "passive"))
      (node (ref "J4") (pin "1") (pinfunction "1_1") (pintype "bidirectional"))
    )
    (net (code "46") (name "Net-(C65-Pad2)") (class "Default")
      (node (ref "C65") (pin "2") (pinfunction "2_2") (pintype "passive"))
      (node (ref "R40") (pin "2") (pinfunction "2_2") (pintype "passive"))
      (node (ref "R64") (pin "2") (pinfunction "2_2") (pintype "passive"))
    )
    (net (code "47") (name "Net-(C67-Pad2)") (class "Default")
      (node (ref "C67") (pin "2") (pinfunction "2_2") (pintype "passive"))
      (node (ref "R42") (pin "1") (pinfunction "1_1") (pintype "passive"))
    )
    (net (code "48") (name "Net-(IC2-CP)") (class "Default")
      (node (ref "C64") (pin "2") (pinfunction "2_2") (pintype "passive"))
      (node (ref "IC2") (pin "6") (pinfunction "CP_6") (pintype "output"))
      (node (ref "R40") (pin "1") (pinfunction "1_1") (pintype "passive"))
      (node (ref "R42") (pin "2") (pinfunction "2_2") (pintype "passive"))
    )
    (net (code "49") (name "Net-(IC2-CPRSET)") (class "Default")
      (node (ref "IC2") (pin "63") (pinfunction "CPRSET_63") (pintype "input"))
      (node (ref "R29") (pin "1") (pinfunction "1_1") (pintype "passive"))
    )
    (net (code "50") (name "Net-(IC2-RSET)") (class "Default")
      (node (ref "IC2") (pin "61") (pinfunction "RSET_61") (pintype "input"))
      (node (ref "R30") (pin "1") (pinfunction "1_1") (pintype "passive"))
    )
    (net (code "51") (name "Net-(IC26-EN)") (class "Default")
      (node (ref "IC26") (pin "8") (pinfunction "EN_8") (pintype "input"))
      (node (ref "R55") (pin "2") (pinfunction "2_2") (pintype "passive"))
    )
    (net (code "52") (name "Net-(IC26-SCL2)") (class "Default")
      (node (ref "IC26") (pin "6") (pinfunction "SCL2_6") (pintype "bidirectional"))
      (node (ref "OSC2") (pin "8") (pinfunction "SCL_8") (pintype "input"))
      (node (ref "R13") (pin "1") (pinfunction "1_1") (pintype "passive"))
    )
    (net (code "53") (name "Net-(IC26-SDA2)") (class "Default")
      (node (ref "IC26") (pin "5") (pinfunction "SDA2_5") (pintype "bidirectional"))
      (node (ref "OSC2") (pin "7") (pinfunction "SDA_7") (pintype "bidirectional"))
      (node (ref "R12") (pin "1") (pinfunction "1_1") (pintype "passive"))
    )
    (net (code "54") (name "Net-(OSC1-OUT)") (class "Default")
      (node (ref "OSC1") (pin "3") (pinfunction "OUT_3") (pintype "output"))
      (node (ref "R26") (pin "1") (pinfunction "1_1") (pintype "passive"))
    )
    (net (code "55") (name "Net-(OSC1-VC)") (class "Default")
      (node (ref "C66") (pin "2") (pinfunction "2_2") (pintype "passive"))
      (node (ref "OSC1") (pin "1") (pinfunction "VC_1") (pintype "input"))
      (node (ref "OSC2") (pin "1") (pinfunction "Vc_1") (pintype "input"))
      (node (ref "R64") (pin "1") (pinfunction "1_1") (pintype "passive"))
    )
    (net (code "56") (name "Net-(OSC1-VDD)") (class "Default")
      (node (ref "C38") (pin "1") (pinfunction "1_1") (pintype "passive"))
      (node (ref "C52") (pin "1") (pinfunction "1_1") (pintype "passive"))
      (node (ref "L1") (pin "2") (pinfunction "2_2") (pintype "passive"))
      (node (ref "OSC1") (pin "4") (pinfunction "VDD_4") (pintype "power_in"))
    )
    (net (code "57") (name "Net-(OSC2-CLK+)") (class "Default")
      (node (ref "OSC2") (pin "4") (pinfunction "CLK+_4") (pintype "output"))
      (node (ref "R72") (pin "1") (pinfunction "1_1") (pintype "passive"))
    )
    (net (code "58") (name "Net-(OSC2-CLK-)") (class "Default")
      (node (ref "OSC2") (pin "5") (pinfunction "CLK-_5") (pintype "output"))
      (node (ref "R73") (pin "1") (pinfunction "1_1") (pintype "passive"))
    )
    (net (code "59") (name "Net-(OSC2-VDD)") (class "Default")
      (node (ref "C59") (pin "2") (pinfunction "2_2") (pintype "passive"))
      (node (ref "C63") (pin "1") (pinfunction "1_1") (pintype "passive"))
      (node (ref "L9") (pin "1") (pinfunction "1_1") (pintype "passive"))
      (node (ref "OSC2") (pin "6") (pinfunction "VDD_6") (pintype "power_in"))
    )
    (net (code "60") (name "Net-(TR6-P)") (class "Default")
      (node (ref "J4") (pin "2") (pinfunction "2_2") (pintype "bidirectional"))
      (node (ref "R28") (pin "1") (pinfunction "1_1") (pintype "passive"))
      (node (ref "TR6") (pin "4") (pinfunction "P_4") (pintype "passive"))
    )
    (net (code "61") (name "Net-(TR6-PDOT)") (class "Default")
      (node (ref "C61") (pin "1") (pinfunction "1_1") (pintype "passive"))
      (node (ref "TR6") (pin "6") (pinfunction "PDOT_6") (pintype "passive"))
    )
    (net (code "62") (name "P3V3CLK") (class "Default")
      (node (ref "C26") (pin "2") (pinfunction "2_2") (pintype "passive"))
      (node (ref "C27") (pin "2") (pinfunction "2_2") (pintype "passive"))
      (node (ref "C28") (pin "2") (pinfunction "2_2") (pintype "passive"))
      (node (ref "C29") (pin "2") (pinfunction "2_2") (pintype "passive"))
      (node (ref "C30") (pin "2") (pinfunction "2_2") (pintype "passive"))
      (node (ref "C31") (pin "2") (pinfunction "2_2") (pintype "passive"))
      (node (ref "C32") (pin "2") (pinfunction "2_2") (pintype "passive"))
      (node (ref "C34") (pin "2") (pinfunction "2_2") (pintype "passive"))
      (node (ref "C35") (pin "2") (pinfunction "2_2") (pintype "passive"))
      (node (ref "C37") (pin "2") (pinfunction "2_2") (pintype "passive"))
      (node (ref "C47") (pin "2") (pinfunction "2_2") (pintype "passive"))
      (node (ref "C48") (pin "2") (pinfunction "2_2") (pintype "passive"))
      (node (ref "C49") (pin "2") (pinfunction "2_2") (pintype "passive"))
      (node (ref "C50") (pin "2") (pinfunction "2_2") (pintype "passive"))
      (node (ref "C62") (pin "2") (pinfunction "2_2") (pintype "passive"))
      (node (ref "IC2") (pin "13") (pinfunction "VS_13") (pintype "power_in"))
      (node (ref "IC2") (pin "23") (pinfunction "VS_23") (pintype "power_in"))
      (node (ref "IC2") (pin "26") (pinfunction "VS_26") (pintype "power_in"))
      (node (ref "IC2") (pin "30") (pinfunction "VS_30") (pintype "power_in"))
      (node (ref "IC2") (pin "31") (pinfunction "VS_31") (pintype "power_in"))
      (node (ref "IC2") (pin "33") (pinfunction "VS_33") (pintype "power_in"))
      (node (ref "IC2") (pin "36") (pinfunction "VS_36") (pintype "power_in"))
      (node (ref "IC2") (pin "37") (pinfunction "VS_37") (pintype "power_in"))
      (node (ref "IC2") (pin "4") (pinfunction "VS_4") (pintype "power_in"))
      (node (ref "IC2") (pin "40") (pinfunction "VS_40") (pintype "power_in"))
      (node (ref "IC2") (pin "41") (pinfunction "VS_41") (pintype "power_in"))
      (node (ref "IC2") (pin "44") (pinfunction "VS_44") (pintype "power_in"))
      (node (ref "IC2") (pin "45") (pinfunction "VS_45") (pintype "power_in"))
      (node (ref "IC2") (pin "48") (pinfunction "VS_48") (pintype "power_in"))
      (node (ref "IC2") (pin "5") (pinfunction "VCP_5") (pintype "power_in"))
      (node (ref "IC2") (pin "51") (pinfunction "VS_51") (pintype "power_in"))
      (node (ref "IC2") (pin "52") (pinfunction "VS_52") (pintype "power_in"))
      (node (ref "IC2") (pin "56") (pinfunction "VS_56") (pintype "power_in"))
      (node (ref "IC2") (pin "59") (pinfunction "VS_59") (pintype "power_in"))
      (node (ref "IC2") (pin "60") (pinfunction "VS_60") (pintype "power_in"))
      (node (ref "IC2") (pin "64") (pinfunction "VS_64") (pintype "power_in"))
      (node (ref "IC2") (pin "9") (pinfunction "VS_9") (pintype "power_in"))
      (node (ref "IC26") (pin "7") (pinfunction "VREF2_7") (pintype "input"))
      (node (ref "IC4") (pin "13") (pinfunction "Vdd_13") (pintype "power_in"))
      (node (ref "IC4") (pin "8") (pinfunction "Vdd_8") (pintype "power_in"))
      (node (ref "L1") (pin "1") (pinfunction "1_1") (pintype "passive"))
      (node (ref "L9") (pin "2") (pinfunction "2_2") (pintype "passive"))
      (node (ref "R12") (pin "2") (pinfunction "2_2") (pintype "passive"))
      (node (ref "R13") (pin "2") (pinfunction "2_2") (pintype "passive"))
      (node (ref "R55") (pin "1") (pinfunction "1_1") (pintype "passive"))
    )
    (net (code "63") (name "VADJ") (class "Default")
      (node (ref "IC26") (pin "2") (pinfunction "VREF1_2") (pintype "input"))
    )
    (net (code "64") (name "unconnected-(IC2-OUT5-Pad43)") (class "Default")
      (node (ref "IC2") (pin "43") (pinfunction "OUT5_43") (pintype "output"))
    )
    (net (code "65") (name "unconnected-(IC2-OUT5B-Pad42)") (class "Default")
      (node (ref "IC2") (pin "42") (pinfunction "OUT5B_42") (pintype "output"))
    )
    (net (code "66") (name "unconnected-(IC2-OUT6-Pad39)") (class "Default")
      (node (ref "IC2") (pin "39") (pinfunction "OUT6_39") (pintype "output"))
    )
    (net (code "67") (name "unconnected-(IC2-OUT6B-Pad38)") (class "Default")
      (node (ref "IC2") (pin "38") (pinfunction "OUT6B_38") (pintype "output"))
    )
    (net (code "68") (name "unconnected-(IC4-nc-Pad7)") (class "Default")
      (node (ref "IC4") (pin "7") (pinfunction "nc_7") (pintype "passive"))
    )
    (net (code "69") (name "unconnected-(IC4-nc-Pad16)") (class "Default")
      (node (ref "IC4") (pin "16") (pinfunction "nc_16") (pintype "passive"))
    )
    (net (code "70") (name "unconnected-(IC4-reserved-Pad5)") (class "Default")
      (node (ref "IC4") (pin "5") (pinfunction "reserved_5") (pintype "passive"))
    )
    (net (code "71") (name "unconnected-(TR6-NU-Pad2)") (class "Default")
      (node (ref "TR6") (pin "2") (pinfunction "NU_2") (pintype "passive"))
    )
  )
)
